# prec_5V_LDO.net
KiCad netlist of a schematic drawn in Altium Designer
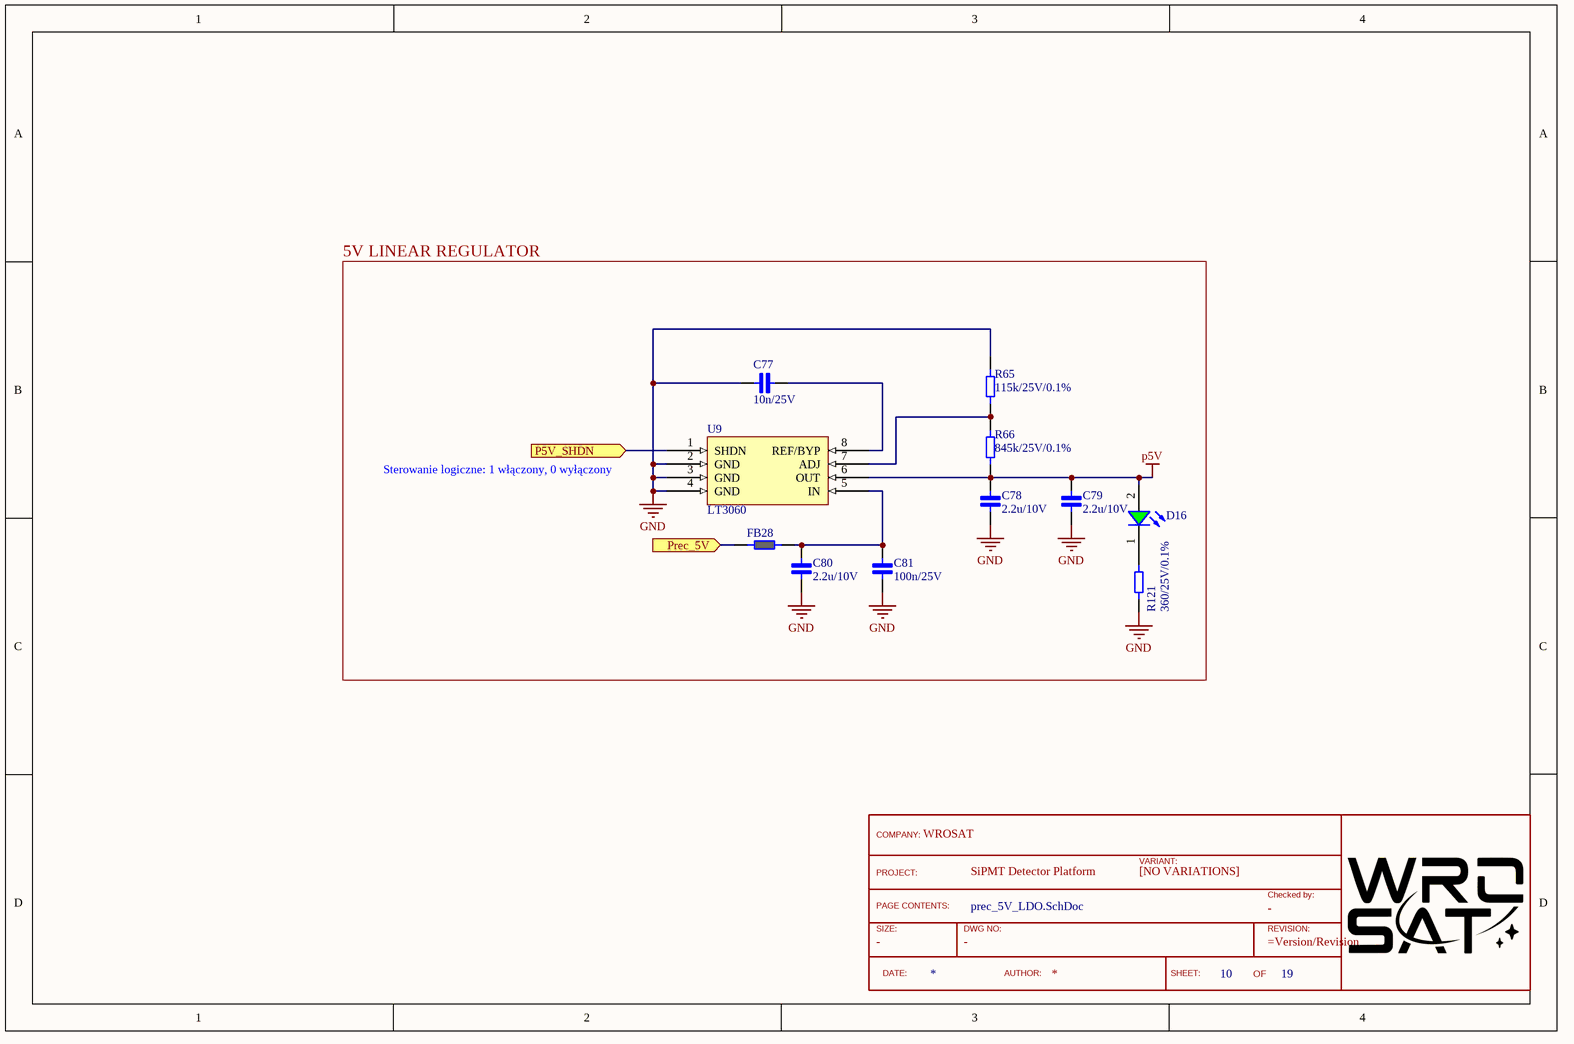
[diagram p0: prec_5V_LDO.SchDoc]

(export (version "E")
  (design (tool "Eeschema 10.0.6"))
  (components
    (comp (ref "C77")
      (value "10n/25V")
      (footprint "Cap_0402")
      (description "Ceramic Capacitor 10n / 0402 / 25V / ±5%, Wurth Elektronik MLCC")
      (libsource (lib "Cubesat_lib") (part "Cap_0402_10n"))
    )
    (comp (ref "C78")
      (value "2.2u/10V")
      (footprint "Cap_0402")
      (description "Ceramic Capacitor 2.2uF / 0402 / 10V / ±5%, Wurth Elektronik MLCC")
      (libsource (lib "Cubesat_lib") (part "Cap_0402_2.2u"))
    )
    (comp (ref "C79")
      (value "2.2u/10V")
      (footprint "Cap_0402")
      (description "Ceramic Capacitor 2.2uF / 0402 / 10V / ±5%, Wurth Elektronik MLCC")
      (libsource (lib "Cubesat_lib") (part "Cap_0402_2.2u"))
    )
    (comp (ref "C80")
      (value "2.2u/10V")
      (footprint "Cap_0402")
      (description "Ceramic Capacitor 2.2uF / 0402 / 10V / ±5%, Wurth Elektronik MLCC")
      (libsource (lib "Cubesat_lib") (part "Cap_0402_2.2u"))
    )
    (comp (ref "C81")
      (value "100n/25V")
      (footprint "Cap_0402")
      (description "Ceramic Capacitor 100n / 0402 / 25V / ±5%, Wurth Elektronik MLCC")
      (libsource (lib "Cubesat_lib") (part "Cap_0402_100n"))
    )
    (comp (ref "D16")
      (value "Green, 3.2V")
      (footprint "WL-SMCW_0603_H=0.7mm")
      (description "WL-SMCW SMT Mono-color Chip LED Waterclear, size 0603, Green, 3.2V, 140deg")
      (fields (field (name "PART NUMBER") "150060GS75000") (field (name "PUBLISHER") "Wurth Elektronik"))
      (libsource (lib "LEDS") (part "150060GS75000"))
    )
    (comp (ref "FB28")
      (value "Ferrite_bead_0402")
      (footprint "FERRITE_0402")
      (description "Ferrite bead, wurth 74269241102")
      (libsource (lib "Cubesat_lib") (part "Ferrite_bead_0402"))
    )
    (comp (ref "R65")
      (value "115k/25V/0.1%")
      (footprint "RES_0402")
      (description "Vishay, thin film resistor 115k/25V/0.1%")
      (libsource (lib "Cubesat_lib") (part "Res_0402_115k"))
    )
    (comp (ref "R66")
      (value "845k/25V/0.1%")
      (footprint "RES_0402")
      (description "Vishay, thin film resistor 845k/25V/0.1%")
      (libsource (lib "Cubesat_lib") (part "Res_0402_845k"))
    )
    (comp (ref "R121")
      (value "360/25V/0.1%")
      (footprint "RES_0402")
      (description "Vishay, thin film resistor 1/25V/0.1%")
      (libsource (lib "Cubesat_lib") (part "Res_0402_1"))
    )
    (comp (ref "U9")
      (value "LT3060")
      (footprint "TS8")
      (description "45V VIN, Micropower,\r\nLow Noise, 100mA Low\r\nDropout, Linear Regulator")
      (libsource (lib "Cubesat_lib") (part "Lt3060"))
    )
  )
  (nets
    (net (code "1") (name "/P5V_SHDN") (class "Default")
      (node (ref "U9") (pin "1") (pinfunction "SHDN_1") (pintype "input"))
    )
    (net (code "2") (name "/Prec_5V") (class "Default")
      (node (ref "FB28") (pin "1") (pinfunction "1_1") (pintype "passive"))
    )
    (net (code "3") (name "GND") (class "Default")
      (node (ref "C77") (pin "2") (pinfunction "2_2") (pintype "passive"))
      (node (ref "C78") (pin "1") (pinfunction "1_1") (pintype "passive"))
      (node (ref "C79") (pin "1") (pinfunction "1_1") (pintype "passive"))
      (node (ref "C80") (pin "1") (pinfunction "1_1") (pintype "passive"))
      (node (ref "C81") (pin "1") (pinfunction "1_1") (pintype "passive"))
      (node (ref "R121") (pin "1") (pinfunction "1_1") (pintype "passive"))
      (node (ref "R65") (pin "2") (pinfunction "2_2") (pintype "passive"))
      (node (ref "U9") (pin "2") (pinfunction "GND_2") (pintype "input"))
      (node (ref "U9") (pin "3") (pinfunction "GND_3") (pintype "input"))
      (node (ref "U9") (pin "4") (pinfunction "GND_4") (pintype "input"))
    )
    (net (code "4") (name "Net-(D16-K)") (class "Default")
      (node (ref "D16") (pin "1") (pinfunction "K_1") (pintype "passive"))
      (node (ref "R121") (pin "2") (pinfunction "2_2") (pintype "passive"))
    )
    (net (code "5") (name "Net-(U9-ADJ)") (class "Default")
      (node (ref "R65") (pin "1") (pinfunction "1_1") (pintype "passive"))
      (node (ref "R66") (pin "2") (pinfunction "2_2") (pintype "passive"))
      (node (ref "U9") (pin "7") (pinfunction "ADJ_7") (pintype "input"))
    )
    (net (code "6") (name "Net-(U9-IN)") (class "Default")
      (node (ref "C80") (pin "2") (pinfunction "2_2") (pintype "passive"))
      (node (ref "C81") (pin "2") (pinfunction "2_2") (pintype "passive"))
      (node (ref "FB28") (pin "2") (pinfunction "2_2") (pintype "passive"))
      (node (ref "U9") (pin "5") (pinfunction "IN_5") (pintype "input"))
    )
    (net (code "7") (name "Net-(U9-REF{slash}BYP)") (class "Default")
      (node (ref "C77") (pin "1") (pinfunction "1_1") (pintype "passive"))
      (node (ref "U9") (pin "8") (pinfunction "REF/BYP_8") (pintype "input"))
    )
    (net (code "8") (name "p5V") (class "Default")
      (node (ref "C78") (pin "2") (pinfunction "2_2") (pintype "passive"))
      (node (ref "C79") (pin "2") (pinfunction "2_2") (pintype "passive"))
      (node (ref "D16") (pin "2") (pinfunction "A_2") (pintype "passive"))
      (node (ref "R66") (pin "1") (pinfunction "1_1") (pintype "passive"))
      (node (ref "U9") (pin "6") (pinfunction "OUT_6") (pintype "input"))
    )
  )
)
